# rpicam.net
KiCad netlist of a schematic drawn in EAGLE
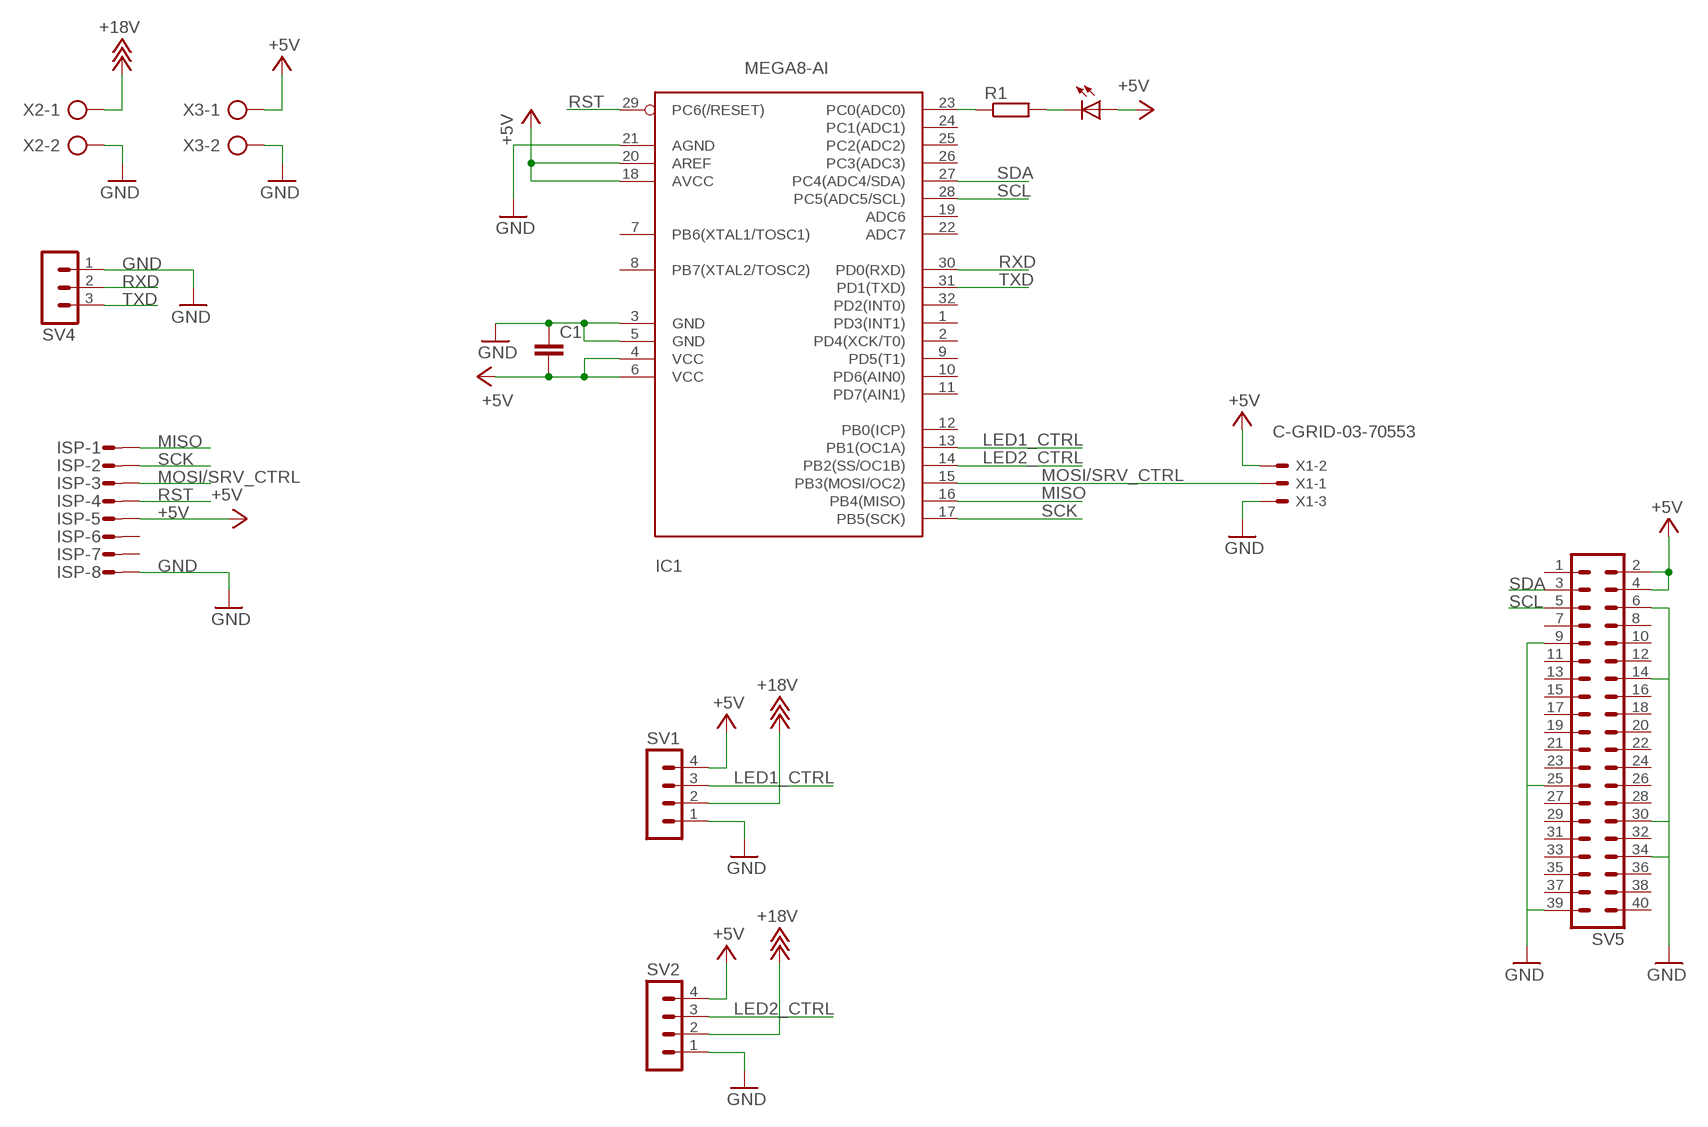
[diagram p0: schematic, sheet 1]

(export (version "E")
  (design (tool "Eeschema 10.0.6"))
  (components
    (comp (ref "C1")
      (value "C-EUC0805")
      (footprint "eagle-import:C0805")
      (libsource (lib "eagle-import") (part "C-EUC0805"))
    )
    (comp (ref "IC1")
      (value "MEGA8-AI")
      (footprint "eagle-import:TQFP32-08")
      (libsource (lib "eagle-import") (part "MEGA8-AI"))
    )
    (comp (ref "ISP")
      (value "MICROMATCH-8")
      (footprint "eagle-import:MICROMATCH-8")
      (fields (field (name "MF") "FARNELL") (field (name "MPN") "7-215464-8"))
      (libsource (lib "eagle-import") (part "MICROMATCH-8"))
    )
    (comp (ref "LED1")
      (value "LEDCHIP-LED0805")
      (footprint "eagle-import:CHIP-LED0805")
      (libsource (lib "eagle-import") (part "LEDCHIP-LED0805"))
    )
    (comp (ref "R1")
      (value "R-EU_R0805")
      (footprint "eagle-import:R0805")
      (libsource (lib "eagle-import") (part "R-EU_R0805"))
    )
    (comp (ref "SV1")
      (value "MA04-1")
      (footprint "eagle-import:MA04-1")
      (libsource (lib "eagle-import") (part "MA04-1"))
    )
    (comp (ref "SV2")
      (value "MA04-1")
      (footprint "eagle-import:MA04-1")
      (libsource (lib "eagle-import") (part "MA04-1"))
    )
    (comp (ref "SV4")
      (value "MA03-1")
      (footprint "eagle-import:MA03-1")
      (libsource (lib "eagle-import") (part "MA03-1"))
    )
    (comp (ref "SV5")
      (value "MA20-2")
      (footprint "eagle-import:MA20-2")
      (libsource (lib "eagle-import") (part "MA20-2"))
    )
    (comp (ref "X1")
      (value "C-GRID-03-70553")
      (footprint "eagle-import:70553-03")
      (libsource (lib "eagle-import") (part "C-GRID-03-70553"))
    )
    (comp (ref "X2")
      (value "AK500/2")
      (footprint "eagle-import:AK500_2")
      (libsource (lib "eagle-import") (part "AK500/2"))
    )
    (comp (ref "X3")
      (value "AK500/2")
      (footprint "eagle-import:AK500_2")
      (libsource (lib "eagle-import") (part "AK500/2"))
    )
  )
  (nets
    (net (code "1") (name "+5V") (class "Default")
      (node (ref "C1") (pin "2") (pinfunction "2_2") (pintype "passive"))
      (node (ref "IC1") (pin "18") (pinfunction "AVCC_18") (pintype "power_in"))
      (node (ref "IC1") (pin "20") (pinfunction "AREF_20") (pintype "passive"))
      (node (ref "IC1") (pin "4") (pinfunction "VCC_4") (pintype "power_in"))
      (node (ref "IC1") (pin "6") (pinfunction "VCC_6") (pintype "power_in"))
      (node (ref "ISP") (pin "5") (pinfunction "S_5") (pintype "passive"))
      (node (ref "LED1") (pin "A") (pinfunction "A_A") (pintype "passive"))
      (node (ref "SV1") (pin "4") (pinfunction "4_4") (pintype "passive"))
      (node (ref "SV2") (pin "4") (pinfunction "4_4") (pintype "passive"))
      (node (ref "SV5") (pin "2") (pinfunction "2_2") (pintype "passive"))
      (node (ref "SV5") (pin "4") (pinfunction "4_4") (pintype "passive"))
      (node (ref "X1") (pin "2") (pinfunction "S_2") (pintype "passive"))
      (node (ref "X3") (pin "1") (pinfunction "KL_1") (pintype "passive"))
    )
    (net (code "2") (name "+18V") (class "Default")
      (node (ref "SV1") (pin "2") (pinfunction "2_2") (pintype "passive"))
      (node (ref "SV2") (pin "2") (pinfunction "2_2") (pintype "passive"))
      (node (ref "X2") (pin "1") (pinfunction "KL_1") (pintype "passive"))
    )
    (net (code "3") (name "/LED1_CTRL") (class "Default")
      (node (ref "IC1") (pin "13") (pinfunction "PB1(OC1A)_13") (pintype "bidirectional"))
      (node (ref "SV1") (pin "3") (pinfunction "3_3") (pintype "passive"))
    )
    (net (code "4") (name "/LED2_CTRL") (class "Default")
      (node (ref "IC1") (pin "14") (pinfunction "PB2(SS/OC1B)_14") (pintype "bidirectional"))
      (node (ref "SV2") (pin "3") (pinfunction "3_3") (pintype "passive"))
    )
    (net (code "5") (name "/MISO") (class "Default")
      (node (ref "IC1") (pin "16") (pinfunction "PB4(MISO)_16") (pintype "bidirectional"))
      (node (ref "ISP") (pin "1") (pinfunction "S_1") (pintype "passive"))
    )
    (net (code "6") (name "/MOSI{slash}SRV_CTRL") (class "Default")
      (node (ref "IC1") (pin "15") (pinfunction "PB3(MOSI/OC2)_15") (pintype "bidirectional"))
      (node (ref "ISP") (pin "3") (pinfunction "S_3") (pintype "passive"))
      (node (ref "X1") (pin "1") (pinfunction "S_1") (pintype "passive"))
    )
    (net (code "7") (name "/RST") (class "Default")
      (node (ref "IC1") (pin "29") (pinfunction "PC6(/RESET)_29") (pintype "bidirectional"))
      (node (ref "ISP") (pin "4") (pinfunction "S_4") (pintype "passive"))
    )
    (net (code "8") (name "/RXD") (class "Default")
      (node (ref "IC1") (pin "30") (pinfunction "PD0(RXD)_30") (pintype "bidirectional"))
      (node (ref "SV4") (pin "2") (pinfunction "2_2") (pintype "passive"))
    )
    (net (code "9") (name "/SCK") (class "Default")
      (node (ref "IC1") (pin "17") (pinfunction "PB5(SCK)_17") (pintype "bidirectional"))
      (node (ref "ISP") (pin "2") (pinfunction "S_2") (pintype "passive"))
    )
    (net (code "10") (name "/SCL") (class "Default")
      (node (ref "IC1") (pin "28") (pinfunction "PC5(ADC5/SCL)_28") (pintype "bidirectional"))
      (node (ref "SV5") (pin "5") (pinfunction "5_5") (pintype "passive"))
    )
    (net (code "11") (name "/SDA") (class "Default")
      (node (ref "IC1") (pin "27") (pinfunction "PC4(ADC4/SDA)_27") (pintype "bidirectional"))
      (node (ref "SV5") (pin "3") (pinfunction "3_3") (pintype "passive"))
    )
    (net (code "12") (name "/TXD") (class "Default")
      (node (ref "IC1") (pin "31") (pinfunction "PD1(TXD)_31") (pintype "bidirectional"))
      (node (ref "SV4") (pin "3") (pinfunction "3_3") (pintype "passive"))
    )
    (net (code "13") (name "GND") (class "Default")
      (node (ref "C1") (pin "1") (pinfunction "1_1") (pintype "passive"))
      (node (ref "IC1") (pin "21") (pinfunction "AGND_21") (pintype "power_in"))
      (node (ref "IC1") (pin "3") (pinfunction "GND_3") (pintype "power_in"))
      (node (ref "IC1") (pin "5") (pinfunction "GND_5") (pintype "power_in"))
      (node (ref "ISP") (pin "8") (pinfunction "S_8") (pintype "passive"))
      (node (ref "SV1") (pin "1") (pinfunction "1_1") (pintype "passive"))
      (node (ref "SV2") (pin "1") (pinfunction "1_1") (pintype "passive"))
      (node (ref "SV4") (pin "1") (pinfunction "1_1") (pintype "passive"))
      (node (ref "SV5") (pin "14") (pinfunction "14_14") (pintype "passive"))
      (node (ref "SV5") (pin "25") (pinfunction "25_25") (pintype "passive"))
      (node (ref "SV5") (pin "30") (pinfunction "30_30") (pintype "passive"))
      (node (ref "SV5") (pin "34") (pinfunction "34_34") (pintype "passive"))
      (node (ref "SV5") (pin "39") (pinfunction "39_39") (pintype "passive"))
      (node (ref "SV5") (pin "6") (pinfunction "6_6") (pintype "passive"))
      (node (ref "SV5") (pin "9") (pinfunction "9_9") (pintype "passive"))
      (node (ref "X1") (pin "3") (pinfunction "S_3") (pintype "passive"))
      (node (ref "X2") (pin "2") (pinfunction "KL_2") (pintype "passive"))
      (node (ref "X3") (pin "2") (pinfunction "KL_2") (pintype "passive"))
    )
    (net (code "14") (name "Net-(IC1-PC0(ADC0))") (class "Default")
      (node (ref "IC1") (pin "23") (pinfunction "PC0(ADC0)_23") (pintype "bidirectional"))
      (node (ref "R1") (pin "1") (pinfunction "1_1") (pintype "passive"))
    )
    (net (code "15") (name "Net-(LED1-PadC)") (class "Default")
      (node (ref "LED1") (pin "C") (pinfunction "C_C") (pintype "passive"))
      (node (ref "R1") (pin "2") (pinfunction "2_2") (pintype "passive"))
    )
    (net (code "16") (name "unconnected-(IC1-ADC6-Pad19)") (class "Default")
      (node (ref "IC1") (pin "19") (pinfunction "ADC6_19") (pintype "bidirectional"))
    )
    (net (code "17") (name "unconnected-(IC1-ADC7-Pad22)") (class "Default")
      (node (ref "IC1") (pin "22") (pinfunction "ADC7_22") (pintype "bidirectional"))
    )
    (net (code "18") (name "unconnected-(IC1-PB0(ICP)-Pad12)") (class "Default")
      (node (ref "IC1") (pin "12") (pinfunction "PB0(ICP)_12") (pintype "bidirectional"))
    )
    (net (code "19") (name "unconnected-(IC1-PB6(XTAL1{slash}TOSC1)-Pad7)") (class "Default")
      (node (ref "IC1") (pin "7") (pinfunction "PB6(XTAL1/TOSC1)_7") (pintype "bidirectional"))
    )
    (net (code "20") (name "unconnected-(IC1-PB7(XTAL2{slash}TOSC2)-Pad8)") (class "Default")
      (node (ref "IC1") (pin "8") (pinfunction "PB7(XTAL2/TOSC2)_8") (pintype "bidirectional"))
    )
    (net (code "21") (name "unconnected-(IC1-PC1(ADC1)-Pad24)") (class "Default")
      (node (ref "IC1") (pin "24") (pinfunction "PC1(ADC1)_24") (pintype "bidirectional"))
    )
    (net (code "22") (name "unconnected-(IC1-PC2(ADC2)-Pad25)") (class "Default")
      (node (ref "IC1") (pin "25") (pinfunction "PC2(ADC2)_25") (pintype "bidirectional"))
    )
    (net (code "23") (name "unconnected-(IC1-PC3(ADC3)-Pad26)") (class "Default")
      (node (ref "IC1") (pin "26") (pinfunction "PC3(ADC3)_26") (pintype "bidirectional"))
    )
    (net (code "24") (name "unconnected-(IC1-PD2(INT0)-Pad32)") (class "Default")
      (node (ref "IC1") (pin "32") (pinfunction "PD2(INT0)_32") (pintype "bidirectional"))
    )
    (net (code "25") (name "unconnected-(IC1-PD3(INT1)-Pad1)") (class "Default")
      (node (ref "IC1") (pin "1") (pinfunction "PD3(INT1)_1") (pintype "bidirectional"))
    )
    (net (code "26") (name "unconnected-(IC1-PD4(XCK{slash}T0)-Pad2)") (class "Default")
      (node (ref "IC1") (pin "2") (pinfunction "PD4(XCK/T0)_2") (pintype "bidirectional"))
    )
    (net (code "27") (name "unconnected-(IC1-PD5(T1)-Pad9)") (class "Default")
      (node (ref "IC1") (pin "9") (pinfunction "PD5(T1)_9") (pintype "bidirectional"))
    )
    (net (code "28") (name "unconnected-(IC1-PD6(AIN0)-Pad10)") (class "Default")
      (node (ref "IC1") (pin "10") (pinfunction "PD6(AIN0)_10") (pintype "bidirectional"))
    )
    (net (code "29") (name "unconnected-(IC1-PD7(AIN1)-Pad11)") (class "Default")
      (node (ref "IC1") (pin "11") (pinfunction "PD7(AIN1)_11") (pintype "bidirectional"))
    )
    (net (code "30") (name "unconnected-(ISPF-S-Pad6)") (class "Default")
      (node (ref "ISP") (pin "6") (pinfunction "S_6") (pintype "passive"))
    )
    (net (code "31") (name "unconnected-(ISPG-S-Pad7)") (class "Default")
      (node (ref "ISP") (pin "7") (pinfunction "S_7") (pintype "passive"))
    )
    (net (code "32") (name "unconnected-(SV5-Pad1)") (class "Default")
      (node (ref "SV5") (pin "1") (pinfunction "1_1") (pintype "passive"))
    )
    (net (code "33") (name "unconnected-(SV5-Pad7)") (class "Default")
      (node (ref "SV5") (pin "7") (pinfunction "7_7") (pintype "passive"))
    )
    (net (code "34") (name "unconnected-(SV5-Pad8)") (class "Default")
      (node (ref "SV5") (pin "8") (pinfunction "8_8") (pintype "passive"))
    )
    (net (code "35") (name "unconnected-(SV5-Pad10)") (class "Default")
      (node (ref "SV5") (pin "10") (pinfunction "10_10") (pintype "passive"))
    )
    (net (code "36") (name "unconnected-(SV5-Pad11)") (class "Default")
      (node (ref "SV5") (pin "11") (pinfunction "11_11") (pintype "passive"))
    )
    (net (code "37") (name "unconnected-(SV5-Pad12)") (class "Default")
      (node (ref "SV5") (pin "12") (pinfunction "12_12") (pintype "passive"))
    )
    (net (code "38") (name "unconnected-(SV5-Pad13)") (class "Default")
      (node (ref "SV5") (pin "13") (pinfunction "13_13") (pintype "passive"))
    )
    (net (code "39") (name "unconnected-(SV5-Pad15)") (class "Default")
      (node (ref "SV5") (pin "15") (pinfunction "15_15") (pintype "passive"))
    )
    (net (code "40") (name "unconnected-(SV5-Pad16)") (class "Default")
      (node (ref "SV5") (pin "16") (pinfunction "16_16") (pintype "passive"))
    )
    (net (code "41") (name "unconnected-(SV5-Pad17)") (class "Default")
      (node (ref "SV5") (pin "17") (pinfunction "17_17") (pintype "passive"))
    )
    (net (code "42") (name "unconnected-(SV5-Pad18)") (class "Default")
      (node (ref "SV5") (pin "18") (pinfunction "18_18") (pintype "passive"))
    )
    (net (code "43") (name "unconnected-(SV5-Pad19)") (class "Default")
      (node (ref "SV5") (pin "19") (pinfunction "19_19") (pintype "passive"))
    )
    (net (code "44") (name "unconnected-(SV5-Pad20)") (class "Default")
      (node (ref "SV5") (pin "20") (pinfunction "20_20") (pintype "passive"))
    )
    (net (code "45") (name "unconnected-(SV5-Pad21)") (class "Default")
      (node (ref "SV5") (pin "21") (pinfunction "21_21") (pintype "passive"))
    )
    (net (code "46") (name "unconnected-(SV5-Pad22)") (class "Default")
      (node (ref "SV5") (pin "22") (pinfunction "22_22") (pintype "passive"))
    )
    (net (code "47") (name "unconnected-(SV5-Pad23)") (class "Default")
      (node (ref "SV5") (pin "23") (pinfunction "23_23") (pintype "passive"))
    )
    (net (code "48") (name "unconnected-(SV5-Pad24)") (class "Default")
      (node (ref "SV5") (pin "24") (pinfunction "24_24") (pintype "passive"))
    )
    (net (code "49") (name "unconnected-(SV5-Pad26)") (class "Default")
      (node (ref "SV5") (pin "26") (pinfunction "26_26") (pintype "passive"))
    )
    (net (code "50") (name "unconnected-(SV5-Pad27)") (class "Default")
      (node (ref "SV5") (pin "27") (pinfunction "27_27") (pintype "passive"))
    )
    (net (code "51") (name "unconnected-(SV5-Pad28)") (class "Default")
      (node (ref "SV5") (pin "28") (pinfunction "28_28") (pintype "passive"))
    )
    (net (code "52") (name "unconnected-(SV5-Pad29)") (class "Default")
      (node (ref "SV5") (pin "29") (pinfunction "29_29") (pintype "passive"))
    )
    (net (code "53") (name "unconnected-(SV5-Pad31)") (class "Default")
      (node (ref "SV5") (pin "31") (pinfunction "31_31") (pintype "passive"))
    )
    (net (code "54") (name "unconnected-(SV5-Pad32)") (class "Default")
      (node (ref "SV5") (pin "32") (pinfunction "32_32") (pintype "passive"))
    )
    (net (code "55") (name "unconnected-(SV5-Pad33)") (class "Default")
      (node (ref "SV5") (pin "33") (pinfunction "33_33") (pintype "passive"))
    )
    (net (code "56") (name "unconnected-(SV5-Pad35)") (class "Default")
      (node (ref "SV5") (pin "35") (pinfunction "35_35") (pintype "passive"))
    )
    (net (code "57") (name "unconnected-(SV5-Pad36)") (class "Default")
      (node (ref "SV5") (pin "36") (pinfunction "36_36") (pintype "passive"))
    )
    (net (code "58") (name "unconnected-(SV5-Pad37)") (class "Default")
      (node (ref "SV5") (pin "37") (pinfunction "37_37") (pintype "passive"))
    )
    (net (code "59") (name "unconnected-(SV5-Pad38)") (class "Default")
      (node (ref "SV5") (pin "38") (pinfunction "38_38") (pintype "passive"))
    )
    (net (code "60") (name "unconnected-(SV5-Pad40)") (class "Default")
      (node (ref "SV5") (pin "40") (pinfunction "40_40") (pintype "passive"))
    )
  )
)
